# Schematic.net
KiCad netlist of a schematic drawn in EAGLE
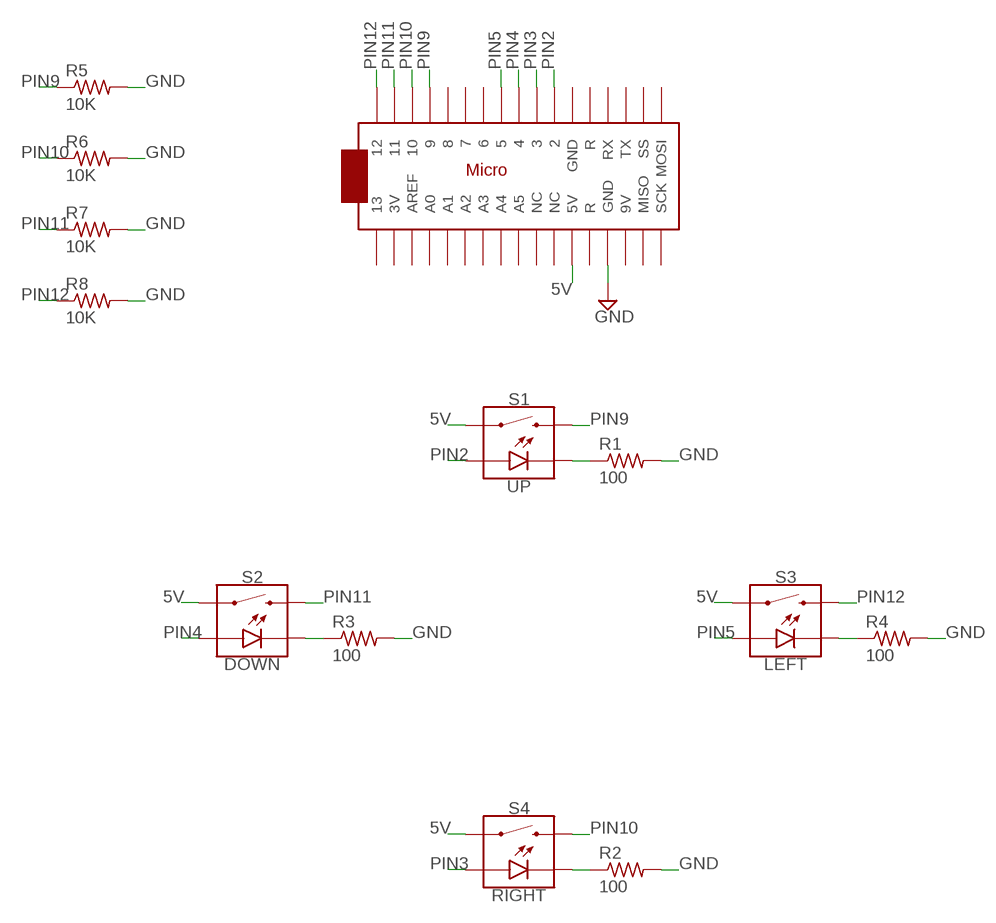
[diagram p0: schematic, sheet 1]

(export (version "E")
  (design (tool "Eeschema 10.0.6"))
  (components
    (comp (ref "R1")
      (value "100")
      (footprint "eagle-import:0207_7")
      (libsource (lib "eagle-import") (part "R-US_0207/7"))
    )
    (comp (ref "R2")
      (value "100")
      (footprint "eagle-import:0207_7")
      (libsource (lib "eagle-import") (part "R-US_0207/7"))
    )
    (comp (ref "R3")
      (value "100")
      (footprint "eagle-import:0207_7")
      (libsource (lib "eagle-import") (part "R-US_0207/7"))
    )
    (comp (ref "R4")
      (value "100")
      (footprint "eagle-import:0207_7")
      (libsource (lib "eagle-import") (part "R-US_0207/7"))
    )
    (comp (ref "R5")
      (value "10K")
      (footprint "eagle-import:0207_7")
      (libsource (lib "eagle-import") (part "R-US_0207/7"))
    )
    (comp (ref "R6")
      (value "10K")
      (footprint "eagle-import:0207_7")
      (libsource (lib "eagle-import") (part "R-US_0207/7"))
    )
    (comp (ref "R7")
      (value "10K")
      (footprint "eagle-import:0207_7")
      (libsource (lib "eagle-import") (part "R-US_0207/7"))
    )
    (comp (ref "R8")
      (value "10K")
      (footprint "eagle-import:0207_7")
      (libsource (lib "eagle-import") (part "R-US_0207/7"))
    )
    (comp (ref "S1")
      (value "UP")
      (footprint "eagle-import:TACTILE_SWITCH_LED_PTH_12MM_KIT")
      (libsource (lib "eagle-import") (part "MOMENTARY-SWITCH-SPST-LED-PTH-12MM-KIT"))
    )
    (comp (ref "S2")
      (value "DOWN")
      (footprint "eagle-import:TACTILE_SWITCH_LED_PTH_12MM_KIT")
      (libsource (lib "eagle-import") (part "MOMENTARY-SWITCH-SPST-LED-PTH-12MM-KIT"))
    )
    (comp (ref "S3")
      (value "LEFT")
      (footprint "eagle-import:TACTILE_SWITCH_LED_PTH_12MM_KIT")
      (libsource (lib "eagle-import") (part "MOMENTARY-SWITCH-SPST-LED-PTH-12MM-KIT"))
    )
    (comp (ref "S4")
      (value "RIGHT")
      (footprint "eagle-import:TACTILE_SWITCH_LED_PTH_12MM_KIT")
      (libsource (lib "eagle-import") (part "MOMENTARY-SWITCH-SPST-LED-PTH-12MM-KIT"))
    )
    (comp (ref "U$1")
      (value "ARDUINOMICRO")
      (footprint "eagle-import:ARDUINOMICRO")
      (libsource (lib "eagle-import") (part "ARDUINOMICRO"))
    )
  )
  (nets
    (net (code "1") (name "/5V") (class "Default")
      (node (ref "S1") (pin "4") (pinfunction "1_4") (pintype "passive"))
      (node (ref "S2") (pin "4") (pinfunction "1_4") (pintype "passive"))
      (node (ref "S3") (pin "4") (pinfunction "1_4") (pintype "passive"))
      (node (ref "S4") (pin "4") (pinfunction "1_4") (pintype "passive"))
      (node (ref "U$1") (pin "P$23") (pinfunction "5V_P$23") (pintype "bidirectional"))
    )
    (net (code "2") (name "/PIN2") (class "Default")
      (node (ref "S1") (pin "A") (pinfunction "A_A") (pintype "passive"))
      (node (ref "U$1") (pin "P$11") (pinfunction "2_P$11") (pintype "bidirectional"))
    )
    (net (code "3") (name "/PIN3") (class "Default")
      (node (ref "S4") (pin "A") (pinfunction "A_A") (pintype "passive"))
      (node (ref "U$1") (pin "P$10") (pinfunction "3_P$10") (pintype "bidirectional"))
    )
    (net (code "4") (name "/PIN4") (class "Default")
      (node (ref "S2") (pin "A") (pinfunction "A_A") (pintype "passive"))
      (node (ref "U$1") (pin "P$9") (pinfunction "4_P$9") (pintype "bidirectional"))
    )
    (net (code "5") (name "/PIN5") (class "Default")
      (node (ref "S3") (pin "A") (pinfunction "A_A") (pintype "passive"))
      (node (ref "U$1") (pin "P$8") (pinfunction "5_P$8") (pintype "bidirectional"))
    )
    (net (code "6") (name "/PIN9") (class "Default")
      (node (ref "R5") (pin "1") (pinfunction "1_1") (pintype "passive"))
      (node (ref "S1") (pin "2") (pinfunction "2_2") (pintype "passive"))
      (node (ref "U$1") (pin "P$4") (pinfunction "9_P$4") (pintype "bidirectional"))
    )
    (net (code "7") (name "/PIN10") (class "Default")
      (node (ref "R6") (pin "1") (pinfunction "1_1") (pintype "passive"))
      (node (ref "S4") (pin "2") (pinfunction "2_2") (pintype "passive"))
      (node (ref "U$1") (pin "P$3") (pinfunction "10_P$3") (pintype "bidirectional"))
    )
    (net (code "8") (name "/PIN11") (class "Default")
      (node (ref "R7") (pin "1") (pinfunction "1_1") (pintype "passive"))
      (node (ref "S2") (pin "2") (pinfunction "2_2") (pintype "passive"))
      (node (ref "U$1") (pin "P$2") (pinfunction "11_P$2") (pintype "bidirectional"))
    )
    (net (code "9") (name "/PIN12") (class "Default")
      (node (ref "R8") (pin "1") (pinfunction "1_1") (pintype "passive"))
      (node (ref "S3") (pin "2") (pinfunction "2_2") (pintype "passive"))
      (node (ref "U$1") (pin "P$1") (pinfunction "12_P$1") (pintype "bidirectional"))
    )
    (net (code "10") (name "GND") (class "Default")
      (node (ref "R1") (pin "2") (pinfunction "2_2") (pintype "passive"))
      (node (ref "R2") (pin "2") (pinfunction "2_2") (pintype "passive"))
      (node (ref "R3") (pin "2") (pinfunction "2_2") (pintype "passive"))
      (node (ref "R4") (pin "2") (pinfunction "2_2") (pintype "passive"))
      (node (ref "R5") (pin "2") (pinfunction "2_2") (pintype "passive"))
      (node (ref "R6") (pin "2") (pinfunction "2_2") (pintype "passive"))
      (node (ref "R7") (pin "2") (pinfunction "2_2") (pintype "passive"))
      (node (ref "R8") (pin "2") (pinfunction "2_2") (pintype "passive"))
      (node (ref "U$1") (pin "P$12") (pinfunction "GND_P$12") (pintype "bidirectional"))
    )
    (net (code "11") (name "Net-(R1-Pad1)") (class "Default")
      (node (ref "R1") (pin "1") (pinfunction "1_1") (pintype "passive"))
      (node (ref "S1") (pin "C") (pinfunction "C_C") (pintype "passive"))
    )
    (net (code "12") (name "Net-(R2-Pad1)") (class "Default")
      (node (ref "R2") (pin "1") (pinfunction "1_1") (pintype "passive"))
      (node (ref "S4") (pin "C") (pinfunction "C_C") (pintype "passive"))
    )
    (net (code "13") (name "Net-(R3-Pad1)") (class "Default")
      (node (ref "R3") (pin "1") (pinfunction "1_1") (pintype "passive"))
      (node (ref "S2") (pin "C") (pinfunction "C_C") (pintype "passive"))
    )
    (net (code "14") (name "Net-(R4-Pad1)") (class "Default")
      (node (ref "R4") (pin "1") (pinfunction "1_1") (pintype "passive"))
      (node (ref "S3") (pin "C") (pinfunction "C_C") (pintype "passive"))
    )
    (net (code "15") (name "unconnected-(U$1-3V-PadP$33)") (class "Default")
      (node (ref "U$1") (pin "P$33") (pinfunction "3V_P$33") (pintype "bidirectional"))
    )
    (net (code "16") (name "unconnected-(U$1-6-PadP$7)") (class "Default")
      (node (ref "U$1") (pin "P$7") (pinfunction "6_P$7") (pintype "bidirectional"))
    )
    (net (code "17") (name "unconnected-(U$1-7-PadP$6)") (class "Default")
      (node (ref "U$1") (pin "P$6") (pinfunction "7_P$6") (pintype "bidirectional"))
    )
    (net (code "18") (name "unconnected-(U$1-8-PadP$5)") (class "Default")
      (node (ref "U$1") (pin "P$5") (pinfunction "8_P$5") (pintype "bidirectional"))
    )
    (net (code "19") (name "unconnected-(U$1-9V-PadP$20)") (class "Default")
      (node (ref "U$1") (pin "P$20") (pinfunction "9V_P$20") (pintype "bidirectional"))
    )
    (net (code "20") (name "unconnected-(U$1-13-PadP$34)") (class "Default")
      (node (ref "U$1") (pin "P$34") (pinfunction "13_P$34") (pintype "bidirectional"))
    )
    (net (code "21") (name "unconnected-(U$1-A0-PadP$31)") (class "Default")
      (node (ref "U$1") (pin "P$31") (pinfunction "A0_P$31") (pintype "bidirectional"))
    )
    (net (code "22") (name "unconnected-(U$1-A1-PadP$30)") (class "Default")
      (node (ref "U$1") (pin "P$30") (pinfunction "A1_P$30") (pintype "bidirectional"))
    )
    (net (code "23") (name "unconnected-(U$1-A2-PadP$29)") (class "Default")
      (node (ref "U$1") (pin "P$29") (pinfunction "A2_P$29") (pintype "bidirectional"))
    )
    (net (code "24") (name "unconnected-(U$1-A3-PadP$28)") (class "Default")
      (node (ref "U$1") (pin "P$28") (pinfunction "A3_P$28") (pintype "bidirectional"))
    )
    (net (code "25") (name "unconnected-(U$1-A4-PadP$27)") (class "Default")
      (node (ref "U$1") (pin "P$27") (pinfunction "A4_P$27") (pintype "bidirectional"))
    )
    (net (code "26") (name "unconnected-(U$1-A5-PadP$26)") (class "Default")
      (node (ref "U$1") (pin "P$26") (pinfunction "A5_P$26") (pintype "bidirectional"))
    )
    (net (code "27") (name "unconnected-(U$1-AREF-PadP$32)") (class "Default")
      (node (ref "U$1") (pin "P$32") (pinfunction "AREF_P$32") (pintype "bidirectional"))
    )
    (net (code "28") (name "unconnected-(U$1-GND-PadP$21)") (class "Default")
      (node (ref "U$1") (pin "P$21") (pinfunction "GND_P$21") (pintype "bidirectional"))
    )
    (net (code "29") (name "unconnected-(U$1-MISO-PadP$19)") (class "Default")
      (node (ref "U$1") (pin "P$19") (pinfunction "MISO_P$19") (pintype "bidirectional"))
    )
    (net (code "30") (name "unconnected-(U$1-MOSI-PadP$17)") (class "Default")
      (node (ref "U$1") (pin "P$17") (pinfunction "MOSI_P$17") (pintype "bidirectional"))
    )
    (net (code "31") (name "unconnected-(U$1-NC-PadP$24)") (class "Default")
      (node (ref "U$1") (pin "P$24") (pinfunction "NC_P$24") (pintype "bidirectional"))
    )
    (net (code "32") (name "unconnected-(U$1-NC-PadP$25)") (class "Default")
      (node (ref "U$1") (pin "P$25") (pinfunction "NC_P$25") (pintype "bidirectional"))
    )
    (net (code "33") (name "unconnected-(U$1-R-PadP$13)") (class "Default")
      (node (ref "U$1") (pin "P$13") (pinfunction "R_P$13") (pintype "bidirectional"))
    )
    (net (code "34") (name "unconnected-(U$1-R-PadP$22)") (class "Default")
      (node (ref "U$1") (pin "P$22") (pinfunction "R_P$22") (pintype "bidirectional"))
    )
    (net (code "35") (name "unconnected-(U$1-RX-PadP$14)") (class "Default")
      (node (ref "U$1") (pin "P$14") (pinfunction "RX_P$14") (pintype "bidirectional"))
    )
    (net (code "36") (name "unconnected-(U$1-SCK-PadP$18)") (class "Default")
      (node (ref "U$1") (pin "P$18") (pinfunction "SCK_P$18") (pintype "bidirectional"))
    )
    (net (code "37") (name "unconnected-(U$1-SS-PadP$16)") (class "Default")
      (node (ref "U$1") (pin "P$16") (pinfunction "SS_P$16") (pintype "bidirectional"))
    )
    (net (code "38") (name "unconnected-(U$1-TX-PadP$15)") (class "Default")
      (node (ref "U$1") (pin "P$15") (pinfunction "TX_P$15") (pintype "bidirectional"))
    )
  )
)
